# CAN_UCM_updated.net
KiCad netlist of a schematic drawn in Altium Designer
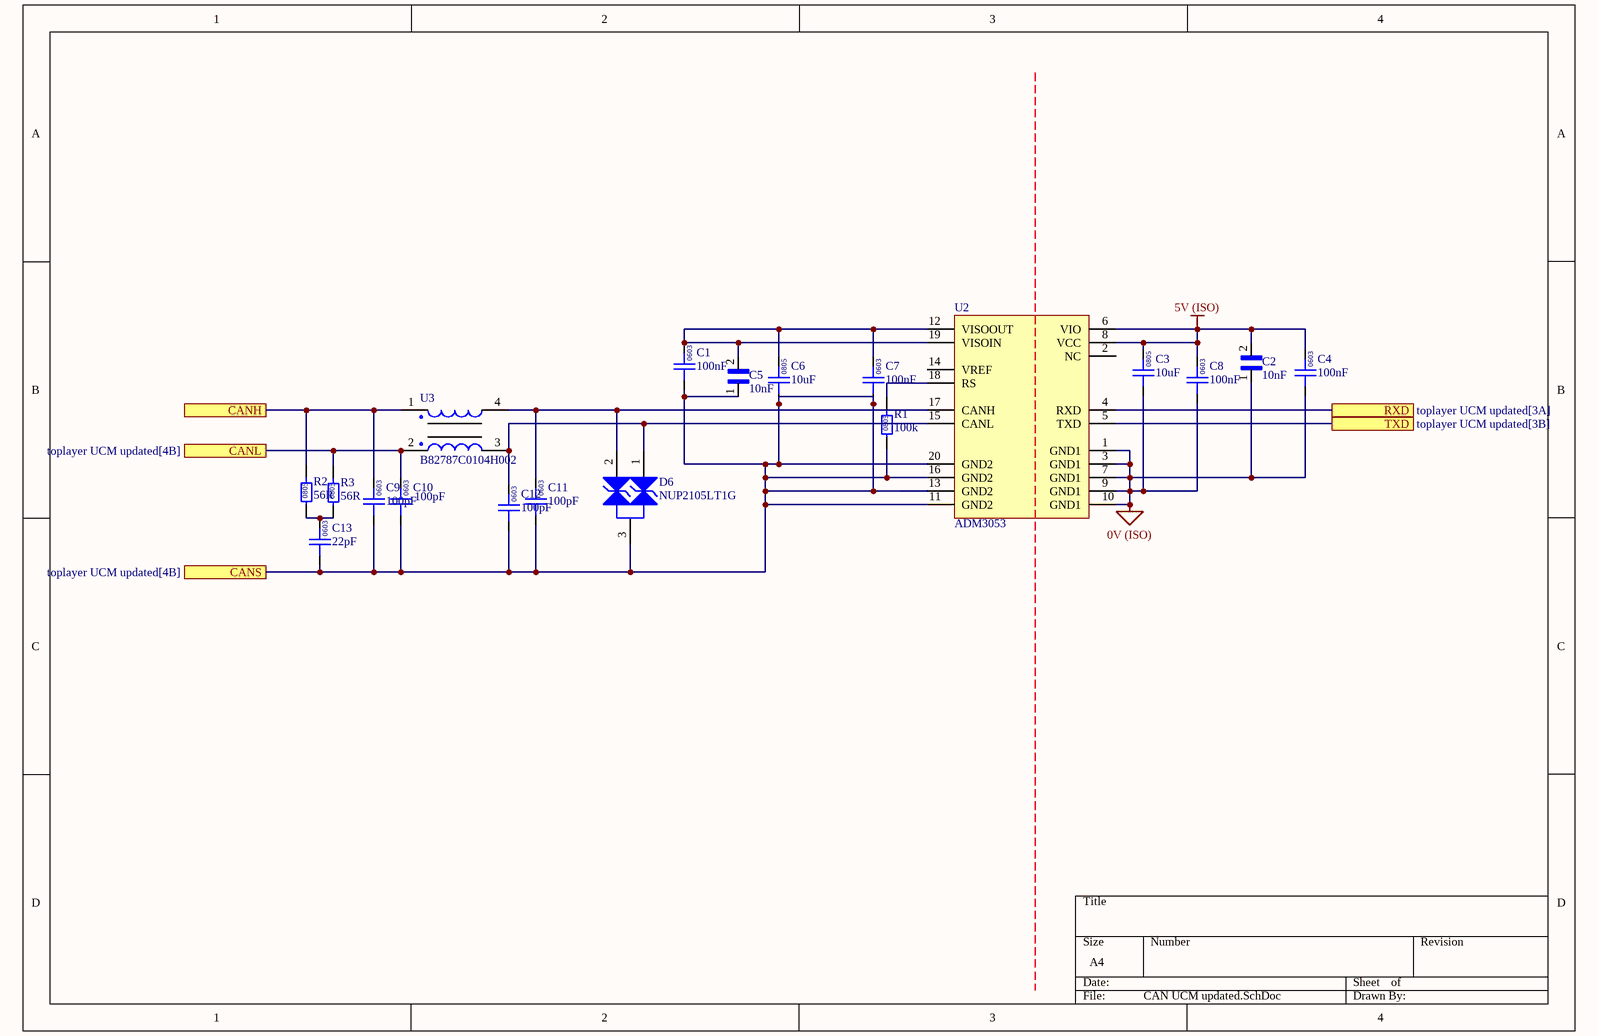
[diagram p0: CAN UCM updated.SchDoc]

(export (version "E")
  (design (tool "Eeschema 10.0.6"))
  (components
    (comp (ref "C1")
      (value "100nF")
      (footprint "0603")
      (fields
        (field (name "PART NUMBER") "GCM188L81H104KA57D")
        (field (name "MANUFACTURER") "muRata")
        (field (name "TOLERANCE") "±10%")
      )
      (libsource (lib "ts_standard_library") (part "Capacitor 0603"))
    )
    (comp (ref "C2")
      (value "10nF")
      (footprint "CAPC3216X95N")
      (description "1206 0.01 uF 100 V Â±5% Tolerance C0G SMT Multilayer Ceramic Capacitor")
      (fields (field (name "MP") "GCM3195C2A103JA16D") (field (name "MF") "Murata Electronics"))
      (libsource (lib "GCM3195C2A103JA16D") (part "GCM3195C2A103JA16D"))
    )
    (comp (ref "C3")
      (value "10uF")
      (footprint "0805")
      (fields
        (field (name "PART NUMBER") "GRM21BR6YA106KE43L")
        (field (name "MANUFACTURER") "muRata")
        (field (name "TOLERANCE") "10%")
      )
      (libsource (lib "ts_standard_library") (part "Capacitor 0805"))
    )
    (comp (ref "C4")
      (value "100nF")
      (footprint "0603")
      (fields
        (field (name "PART NUMBER") "GCM188L81H104KA57D")
        (field (name "MANUFACTURER") "muRata")
        (field (name "TOLERANCE") "±10%")
      )
      (libsource (lib "ts_standard_library") (part "Capacitor 0603"))
    )
    (comp (ref "C5")
      (value "10nF")
      (footprint "CAPC3216X95N")
      (description "1206 0.01 uF 100 V Â±5% Tolerance C0G SMT Multilayer Ceramic Capacitor")
      (fields (field (name "MP") "GCM3195C2A103JA16D") (field (name "MF") "Murata Electronics"))
      (libsource (lib "GCM3195C2A103JA16D") (part "GCM3195C2A103JA16D"))
    )
    (comp (ref "C6")
      (value "10uF")
      (footprint "0805")
      (fields
        (field (name "PART NUMBER") "GRM21BR6YA106KE43L")
        (field (name "MANUFACTURER") "muRata")
        (field (name "TOLERANCE") "10%")
      )
      (libsource (lib "ts_standard_library") (part "Capacitor 0805"))
    )
    (comp (ref "C7")
      (value "100nF")
      (footprint "0603")
      (fields
        (field (name "PART NUMBER") "GCM188L81H104KA57D")
        (field (name "MANUFACTURER") "muRata")
        (field (name "TOLERANCE") "±10%")
      )
      (libsource (lib "ts_standard_library") (part "Capacitor 0603"))
    )
    (comp (ref "C8")
      (value "100nF")
      (footprint "0603")
      (fields
        (field (name "PART NUMBER") "GCM188L81H104KA57D")
        (field (name "MANUFACTURER") "muRata")
        (field (name "TOLERANCE") "±10%")
      )
      (libsource (lib "ts_standard_library") (part "Capacitor 0603"))
    )
    (comp (ref "C9")
      (value "100pF")
      (footprint "0603")
      (fields
        (field (name "PART NUMBER") "GRM1885C1H101JA01D")
        (field (name "MANUFACTURER") "Murata Electronics")
        (field (name "TOLERANCE") "±5%")
      )
      (libsource (lib "ts_standard_library") (part "Capacitor 0603"))
    )
    (comp (ref "C10")
      (value "100pF")
      (footprint "0603")
      (fields
        (field (name "PART NUMBER") "GRM1885C1H101JA01D")
        (field (name "MANUFACTURER") "Murata Electronics")
        (field (name "TOLERANCE") "±5%")
      )
      (libsource (lib "ts_standard_library") (part "Capacitor 0603"))
    )
    (comp (ref "C11")
      (value "100pF")
      (footprint "0603")
      (fields
        (field (name "PART NUMBER") "GRM1885C1H101JA01D")
        (field (name "MANUFACTURER") "Murata Electronics")
        (field (name "TOLERANCE") "±5%")
      )
      (libsource (lib "ts_standard_library") (part "Capacitor 0603"))
    )
    (comp (ref "C12")
      (value "100pF")
      (footprint "0603")
      (fields
        (field (name "PART NUMBER") "GRM1885C1H101JA01D")
        (field (name "MANUFACTURER") "Murata Electronics")
        (field (name "TOLERANCE") "±5%")
      )
      (libsource (lib "ts_standard_library") (part "Capacitor 0603"))
    )
    (comp (ref "C13")
      (value "22pF")
      (footprint "0603")
      (fields
        (field (name "PART NUMBER") "GRM0335C1H220JA01D")
        (field (name "MANUFACTURER") "Murata Electronics")
        (field (name "TOLERANCE") "±5%")
      )
      (libsource (lib "ts_standard_library") (part "Capacitor 0603"))
    )
    (comp (ref "D6")
      (value "NUP2105LT1G")
      (footprint "ONSC-SOT-23-3-318-08_V")
      (description "Dual Line CAN Bus Protector, 3-Pin SOT-23, Pb-Free, Tape and Reel")
      (fields (field (name "MANUFACTURER") "On Semiconductor"))
      (libsource (lib "Components - 29.08.24 - 16.49") (part "CMP-1063-00164-1"))
    )
    (comp (ref "R1")
      (value "100k")
      (footprint "0805")
      (fields
        (field (name "PART NUMBER") "RC0805FR07100KL")
        (field (name "MANUFACTURER") "YAGEO")
        (field (name "TOLERANCE") "0.01")
      )
      (libsource (lib "ts_standard_library") (part "Resistor 0805"))
    )
    (comp (ref "R2")
      (value "56R")
      (footprint "0805")
      (fields
        (field (name "PART NUMBER") "RC0805FR0756RL")
        (field (name "MANUFACTURER") "YAGEO")
        (field (name "TOLERANCE") "0.01")
      )
      (libsource (lib "ts_standard_library") (part "Resistor 0805"))
    )
    (comp (ref "R3")
      (value "56R")
      (footprint "0805")
      (fields
        (field (name "PART NUMBER") "RC0805FR0756RL")
        (field (name "MANUFACTURER") "YAGEO")
        (field (name "TOLERANCE") "0.01")
      )
      (libsource (lib "ts_standard_library") (part "Resistor 0805"))
    )
    (comp (ref "U2")
      (value "ADM3053")
      (footprint "AD SOIC-W 20")
      (description "Isolated CAN Transceiver")
      (fields
        (field (name "MANUFACTURER") "Analogue Devices")
        (field (name "DIGIKEY PART NUMBER") "ADM3053BRWZ-ND")
      )
      (libsource (lib "ts_standard_library") (part "ADM3053"))
    )
    (comp (ref "U3")
      (value "B82787C0104H002")
      (footprint "TDK 4-PC Pad")
      (fields
        (field (name "MANUFACTURER") "EPCOS (TDK)")
        (field (name "DIGIKEY PART NUMBER") "495-4598-1-ND")
      )
      (libsource (lib "ts_standard_library") (part "B82787C0104H002"))
    )
  )
  (nets
    (net (code "1") (name "/CANH") (class "Default")
      (node (ref "C9") (pin "2") (pinfunction "2_2") (pintype "passive"))
      (node (ref "R2") (pin "2") (pinfunction "2_2") (pintype "passive"))
      (node (ref "U3") (pin "1") (pinfunction "1_1") (pintype "passive"))
    )
    (net (code "2") (name "/CANL") (class "Default")
      (node (ref "C10") (pin "2") (pinfunction "2_2") (pintype "passive"))
      (node (ref "R3") (pin "2") (pinfunction "2_2") (pintype "passive"))
      (node (ref "U3") (pin "2") (pinfunction "2_2") (pintype "passive"))
    )
    (net (code "3") (name "/CANS") (class "Default")
      (node (ref "C1") (pin "1") (pinfunction "1_1") (pintype "passive"))
      (node (ref "C10") (pin "1") (pinfunction "1_1") (pintype "passive"))
      (node (ref "C11") (pin "1") (pinfunction "1_1") (pintype "passive"))
      (node (ref "C12") (pin "1") (pinfunction "1_1") (pintype "passive"))
      (node (ref "C13") (pin "1") (pinfunction "1_1") (pintype "passive"))
      (node (ref "C5") (pin "1") (pinfunction "1_1") (pintype "passive"))
      (node (ref "C6") (pin "1") (pinfunction "1_1") (pintype "passive"))
      (node (ref "C7") (pin "1") (pinfunction "1_1") (pintype "passive"))
      (node (ref "C9") (pin "1") (pinfunction "1_1") (pintype "passive"))
      (node (ref "D6") (pin "3") (pinfunction "K_3") (pintype "passive"))
      (node (ref "R1") (pin "1") (pinfunction "1_1") (pintype "passive"))
      (node (ref "U2") (pin "11") (pinfunction "GND2_11") (pintype "passive"))
      (node (ref "U2") (pin "13") (pinfunction "GND2_13") (pintype "passive"))
      (node (ref "U2") (pin "16") (pinfunction "GND2_16") (pintype "passive"))
      (node (ref "U2") (pin "20") (pinfunction "GND2_20") (pintype "passive"))
    )
    (net (code "4") (name "/RXD") (class "Default")
      (node (ref "U2") (pin "4") (pinfunction "RXD_4") (pintype "passive"))
    )
    (net (code "5") (name "/TXD") (class "Default")
      (node (ref "U2") (pin "5") (pinfunction "TXD_5") (pintype "passive"))
    )
    (net (code "6") (name "0V (ISO)") (class "Default")
      (node (ref "C2") (pin "1") (pinfunction "1_1") (pintype "passive"))
      (node (ref "C3") (pin "1") (pinfunction "1_1") (pintype "passive"))
      (node (ref "C4") (pin "1") (pinfunction "1_1") (pintype "passive"))
      (node (ref "C8") (pin "1") (pinfunction "1_1") (pintype "passive"))
      (node (ref "U2") (pin "1") (pinfunction "GND1_1") (pintype "passive"))
      (node (ref "U2") (pin "10") (pinfunction "GND1_10") (pintype "passive"))
      (node (ref "U2") (pin "3") (pinfunction "GND1_3") (pintype "passive"))
      (node (ref "U2") (pin "7") (pinfunction "GND1_7") (pintype "passive"))
      (node (ref "U2") (pin "9") (pinfunction "GND1_9") (pintype "passive"))
    )
    (net (code "7") (name "5V (ISO)") (class "Default")
      (node (ref "C2") (pin "2") (pinfunction "2_2") (pintype "passive"))
      (node (ref "C3") (pin "2") (pinfunction "2_2") (pintype "passive"))
      (node (ref "C4") (pin "2") (pinfunction "2_2") (pintype "passive"))
      (node (ref "C8") (pin "2") (pinfunction "2_2") (pintype "passive"))
      (node (ref "U2") (pin "6") (pinfunction "VIO_6") (pintype "passive"))
      (node (ref "U2") (pin "8") (pinfunction "VCC_8") (pintype "passive"))
    )
    (net (code "8") (name "Net-(C13-Pad2)") (class "Default")
      (node (ref "C13") (pin "2") (pinfunction "2_2") (pintype "passive"))
      (node (ref "R2") (pin "1") (pinfunction "1_1") (pintype "passive"))
      (node (ref "R3") (pin "1") (pinfunction "1_1") (pintype "passive"))
    )
    (net (code "9") (name "Net-(U2-CANH)") (class "Default")
      (node (ref "C11") (pin "2") (pinfunction "2_2") (pintype "passive"))
      (node (ref "D6") (pin "2") (pinfunction "K_2") (pintype "passive"))
      (node (ref "U2") (pin "17") (pinfunction "CANH_17") (pintype "passive"))
      (node (ref "U3") (pin "4") (pinfunction "4_4") (pintype "passive"))
    )
    (net (code "10") (name "Net-(U2-CANL)") (class "Default")
      (node (ref "C12") (pin "2") (pinfunction "2_2") (pintype "passive"))
      (node (ref "D6") (pin "1") (pinfunction "K_1") (pintype "passive"))
      (node (ref "U2") (pin "15") (pinfunction "CANL_15") (pintype "passive"))
      (node (ref "U3") (pin "3") (pinfunction "3_3") (pintype "passive"))
    )
    (net (code "11") (name "Net-(U2-RS)") (class "Default")
      (node (ref "R1") (pin "2") (pinfunction "2_2") (pintype "passive"))
      (node (ref "U2") (pin "18") (pinfunction "RS_18") (pintype "passive"))
    )
    (net (code "12") (name "Net-(U2-VISOIN)") (class "Default")
      (node (ref "C1") (pin "2") (pinfunction "2_2") (pintype "passive"))
      (node (ref "C5") (pin "2") (pinfunction "2_2") (pintype "passive"))
      (node (ref "C6") (pin "2") (pinfunction "2_2") (pintype "passive"))
      (node (ref "C7") (pin "2") (pinfunction "2_2") (pintype "passive"))
      (node (ref "U2") (pin "12") (pinfunction "VISOOUT_12") (pintype "passive"))
      (node (ref "U2") (pin "19") (pinfunction "VISOIN_19") (pintype "passive"))
    )
    (net (code "13") (name "unconnected-(U2-NC-Pad2)") (class "Default")
      (node (ref "U2") (pin "2") (pinfunction "NC_2") (pintype "passive"))
    )
    (net (code "14") (name "unconnected-(U2-VREF-Pad14)") (class "Default")
      (node (ref "U2") (pin "14") (pinfunction "VREF_14") (pintype "passive"))
    )
  )
)
